# Sheet1.net
KiCad netlist of a schematic drawn in Altium Designer
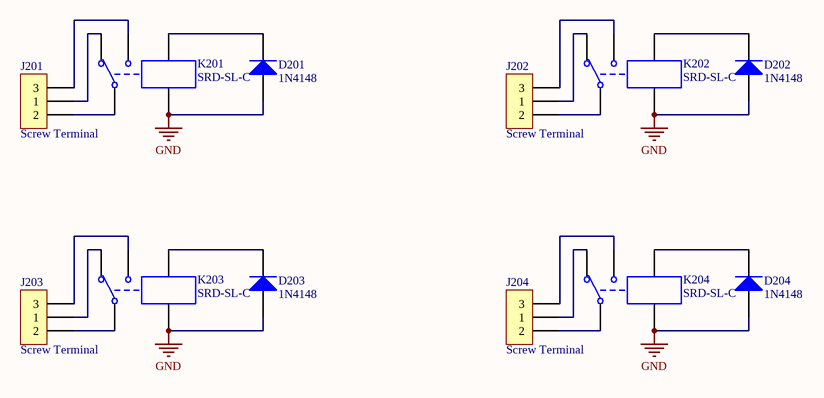
[diagram p0: Sheet1.SchDoc]

(export (version "E")
  (design (tool "Eeschema 10.0.6"))
  (components
    (comp (ref "D201")
      (value "1N4148")
      (footprint "CD2012-0805")
      (libsource (lib "FireFlow Lib") (part "Diode"))
    )
    (comp (ref "D202")
      (value "1N4148")
      (footprint "CD2012-0805")
      (libsource (lib "FireFlow Lib") (part "Diode"))
    )
    (comp (ref "D203")
      (value "1N4148")
      (footprint "CD2012-0805")
      (libsource (lib "FireFlow Lib") (part "Diode"))
    )
    (comp (ref "D204")
      (value "1N4148")
      (footprint "CD2012-0805")
      (libsource (lib "FireFlow Lib") (part "Diode"))
    )
    (comp (ref "J201")
      (value "Screw Terminal")
      (footprint "3pin ST")
      (description "WR-TBL Terminal block - serie 102 - 5.0mm")
      (libsource (lib "FireFlow Lib") (part "3 pin Screw Terminal"))
    )
    (comp (ref "J202")
      (value "Screw Terminal")
      (footprint "3pin ST")
      (description "WR-TBL Terminal block - serie 102 - 5.0mm")
      (libsource (lib "FireFlow Lib") (part "3 pin Screw Terminal"))
    )
    (comp (ref "J203")
      (value "Screw Terminal")
      (footprint "3pin ST")
      (description "WR-TBL Terminal block - serie 102 - 5.0mm")
      (libsource (lib "FireFlow Lib") (part "3 pin Screw Terminal"))
    )
    (comp (ref "J204")
      (value "Screw Terminal")
      (footprint "3pin ST")
      (description "WR-TBL Terminal block - serie 102 - 5.0mm")
      (libsource (lib "FireFlow Lib") (part "3 pin Screw Terminal"))
    )
    (comp (ref "K201")
      (value "SRD-SL-C")
      (footprint "SRD-SL-C")
      (libsource (lib "FireFlow") (part "Relay SRD-SL-C"))
    )
    (comp (ref "K202")
      (value "SRD-SL-C")
      (footprint "SRD-SL-C")
      (libsource (lib "FireFlow") (part "Relay SRD-SL-C"))
    )
    (comp (ref "K203")
      (value "SRD-SL-C")
      (footprint "SRD-SL-C")
      (libsource (lib "FireFlow") (part "Relay SRD-SL-C"))
    )
    (comp (ref "K204")
      (value "SRD-SL-C")
      (footprint "SRD-SL-C")
      (libsource (lib "FireFlow") (part "Relay SRD-SL-C"))
    )
  )
  (nets
    (net (code "1") (name "GND") (class "Default")
      (node (ref "D201") (pin "A") (pinfunction "A_A") (pintype "passive"))
      (node (ref "D202") (pin "A") (pinfunction "A_A") (pintype "passive"))
      (node (ref "D203") (pin "A") (pinfunction "A_A") (pintype "passive"))
      (node (ref "D204") (pin "A") (pinfunction "A_A") (pintype "passive"))
      (node (ref "K201") (pin "2") (pinfunction "2_2") (pintype "passive"))
      (node (ref "K202") (pin "2") (pinfunction "2_2") (pintype "passive"))
      (node (ref "K203") (pin "2") (pinfunction "2_2") (pintype "passive"))
      (node (ref "K204") (pin "2") (pinfunction "2_2") (pintype "passive"))
    )
    (net (code "2") (name "Net-(D201-PadK)") (class "Default")
      (node (ref "D201") (pin "K") (pinfunction "K_K") (pintype "passive"))
      (node (ref "K201") (pin "1") (pinfunction "1_1") (pintype "passive"))
    )
    (net (code "3") (name "Net-(D202-PadK)") (class "Default")
      (node (ref "D202") (pin "K") (pinfunction "K_K") (pintype "passive"))
      (node (ref "K202") (pin "1") (pinfunction "1_1") (pintype "passive"))
    )
    (net (code "4") (name "Net-(D203-PadK)") (class "Default")
      (node (ref "D203") (pin "K") (pinfunction "K_K") (pintype "passive"))
      (node (ref "K203") (pin "1") (pinfunction "1_1") (pintype "passive"))
    )
    (net (code "5") (name "Net-(D204-PadK)") (class "Default")
      (node (ref "D204") (pin "K") (pinfunction "K_K") (pintype "passive"))
      (node (ref "K204") (pin "1") (pinfunction "1_1") (pintype "passive"))
    )
    (net (code "6") (name "Net-(J201-Pad1)") (class "Default")
      (node (ref "J201") (pin "1") (pinfunction "1_1") (pintype "passive"))
      (node (ref "K201") (pin "5") (pinfunction "5_5") (pintype "passive"))
    )
    (net (code "7") (name "Net-(J201-Pad2)") (class "Default")
      (node (ref "J201") (pin "2") (pinfunction "2_2") (pintype "passive"))
      (node (ref "K201") (pin "3") (pinfunction "3_3") (pintype "passive"))
    )
    (net (code "8") (name "Net-(J201-Pad3)") (class "Default")
      (node (ref "J201") (pin "3") (pinfunction "3_3") (pintype "passive"))
      (node (ref "K201") (pin "4") (pinfunction "4_4") (pintype "passive"))
    )
    (net (code "9") (name "Net-(J202-Pad1)") (class "Default")
      (node (ref "J202") (pin "1") (pinfunction "1_1") (pintype "passive"))
      (node (ref "K202") (pin "5") (pinfunction "5_5") (pintype "passive"))
    )
    (net (code "10") (name "Net-(J202-Pad2)") (class "Default")
      (node (ref "J202") (pin "2") (pinfunction "2_2") (pintype "passive"))
      (node (ref "K202") (pin "3") (pinfunction "3_3") (pintype "passive"))
    )
    (net (code "11") (name "Net-(J202-Pad3)") (class "Default")
      (node (ref "J202") (pin "3") (pinfunction "3_3") (pintype "passive"))
      (node (ref "K202") (pin "4") (pinfunction "4_4") (pintype "passive"))
    )
    (net (code "12") (name "Net-(J203-Pad1)") (class "Default")
      (node (ref "J203") (pin "1") (pinfunction "1_1") (pintype "passive"))
      (node (ref "K203") (pin "5") (pinfunction "5_5") (pintype "passive"))
    )
    (net (code "13") (name "Net-(J203-Pad2)") (class "Default")
      (node (ref "J203") (pin "2") (pinfunction "2_2") (pintype "passive"))
      (node (ref "K203") (pin "3") (pinfunction "3_3") (pintype "passive"))
    )
    (net (code "14") (name "Net-(J203-Pad3)") (class "Default")
      (node (ref "J203") (pin "3") (pinfunction "3_3") (pintype "passive"))
      (node (ref "K203") (pin "4") (pinfunction "4_4") (pintype "passive"))
    )
    (net (code "15") (name "Net-(J204-Pad1)") (class "Default")
      (node (ref "J204") (pin "1") (pinfunction "1_1") (pintype "passive"))
      (node (ref "K204") (pin "5") (pinfunction "5_5") (pintype "passive"))
    )
    (net (code "16") (name "Net-(J204-Pad2)") (class "Default")
      (node (ref "J204") (pin "2") (pinfunction "2_2") (pintype "passive"))
      (node (ref "K204") (pin "3") (pinfunction "3_3") (pintype "passive"))
    )
    (net (code "17") (name "Net-(J204-Pad3)") (class "Default")
      (node (ref "J204") (pin "3") (pinfunction "3_3") (pintype "passive"))
      (node (ref "K204") (pin "4") (pinfunction "4_4") (pintype "passive"))
    )
  )
)
